# Proximity.net
KiCad netlist of a schematic drawn in Altium Designer
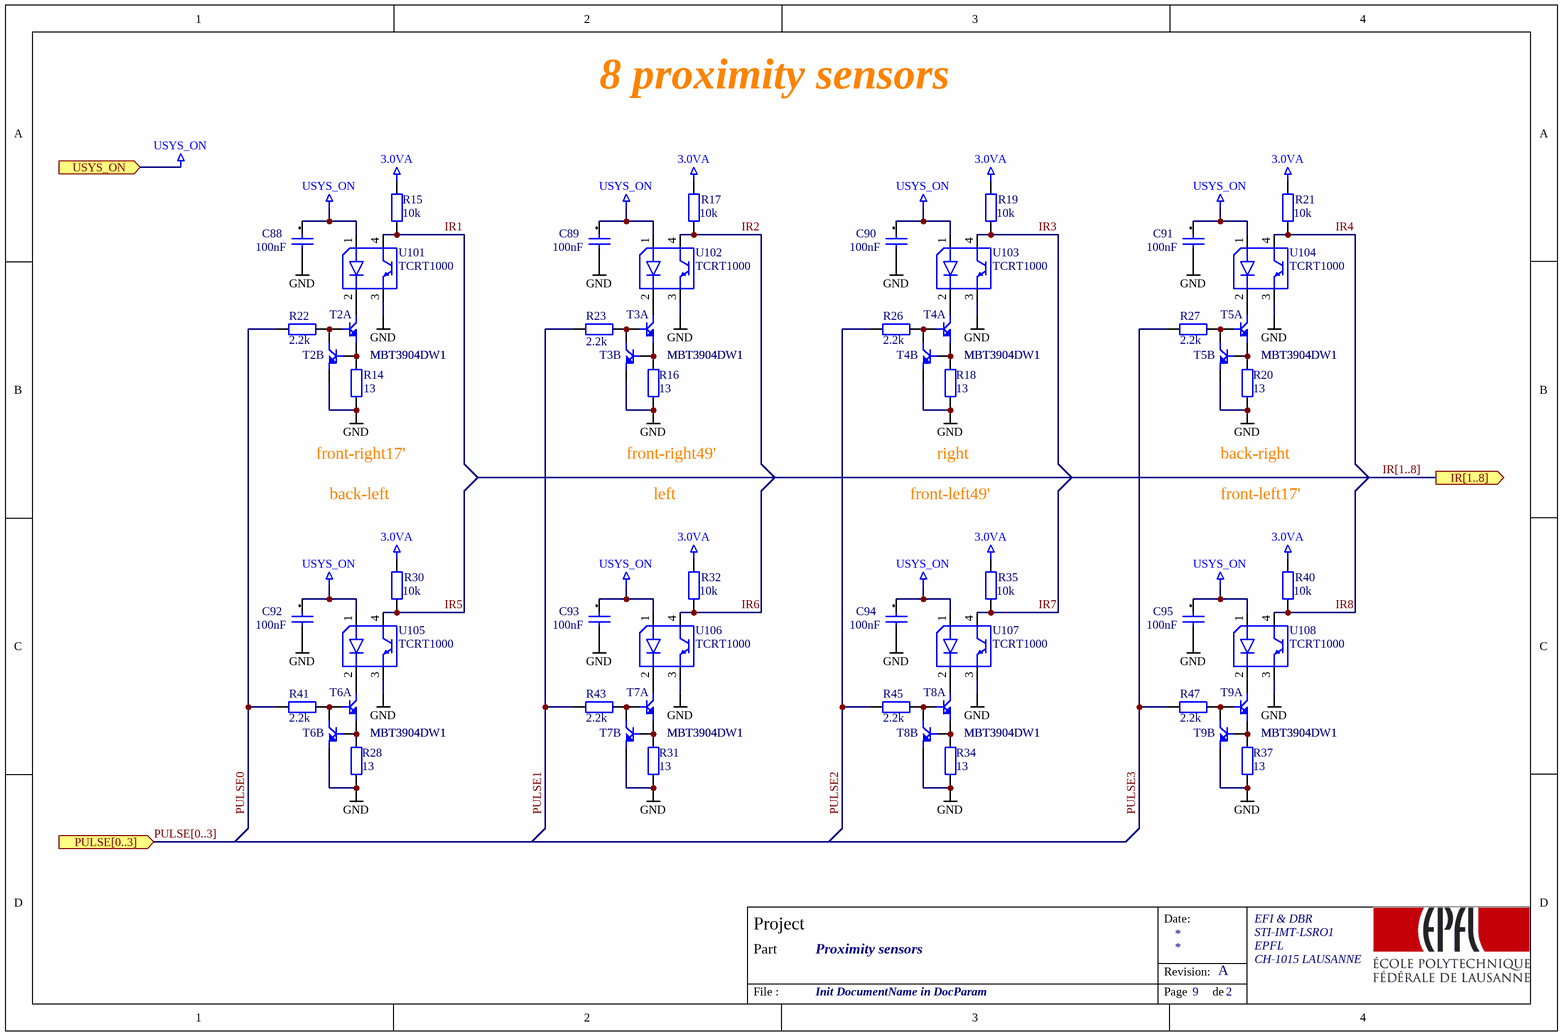
[diagram p0: Proximity.SchDoc]

(export (version "E")
  (design (tool "Eeschema 10.0.6"))
  (components
    (comp (ref "C88")
      (value "100nF")
      (footprint "ROB_0603")
      (description "Capacitor")
      (fields (field (name "MANUFACTURER") "Kemet") (field (name "VOLTAGE") "50"))
      (libsource (lib "LSRO1Altium") (part "CAP-NP"))
    )
    (comp (ref "C89")
      (value "100nF")
      (footprint "ROB_0603")
      (description "Capacitor")
      (fields (field (name "MANUFACTURER") "Kemet") (field (name "VOLTAGE") "50"))
      (libsource (lib "LSRO1Altium") (part "CAP-NP"))
    )
    (comp (ref "C90")
      (value "100nF")
      (footprint "ROB_0603")
      (description "Capacitor")
      (fields (field (name "MANUFACTURER") "Kemet") (field (name "VOLTAGE") "50"))
      (libsource (lib "LSRO1Altium") (part "CAP-NP"))
    )
    (comp (ref "C91")
      (value "100nF")
      (footprint "ROB_0603")
      (description "Capacitor")
      (fields (field (name "MANUFACTURER") "Kemet") (field (name "VOLTAGE") "50"))
      (libsource (lib "LSRO1Altium") (part "CAP-NP"))
    )
    (comp (ref "C92")
      (value "100nF")
      (footprint "ROB_0603")
      (description "Capacitor")
      (fields (field (name "MANUFACTURER") "Kemet") (field (name "VOLTAGE") "50"))
      (libsource (lib "LSRO1Altium") (part "CAP-NP"))
    )
    (comp (ref "C93")
      (value "100nF")
      (footprint "ROB_0603")
      (description "Capacitor")
      (fields (field (name "MANUFACTURER") "Kemet") (field (name "VOLTAGE") "50"))
      (libsource (lib "LSRO1Altium") (part "CAP-NP"))
    )
    (comp (ref "C94")
      (value "100nF")
      (footprint "ROB_0603")
      (description "Capacitor")
      (fields (field (name "MANUFACTURER") "Kemet") (field (name "VOLTAGE") "50"))
      (libsource (lib "LSRO1Altium") (part "CAP-NP"))
    )
    (comp (ref "C95")
      (value "100nF")
      (footprint "ROB_0603")
      (description "Capacitor")
      (fields (field (name "MANUFACTURER") "Kemet") (field (name "VOLTAGE") "50"))
      (libsource (lib "LSRO1Altium") (part "CAP-NP"))
    )
    (comp (ref "R14")
      (value "13")
      (footprint "ROB_0603")
      (description "Resistor")
      (fields (field (name "PUBLISHER") "Altium Limited"))
      (libsource (lib "") (part "Res2_2"))
    )
    (comp (ref "R15")
      (value "10k")
      (footprint "ROB_0603")
      (description "Resistor")
      (fields (field (name "PUBLISHER") "Altium Limited"))
      (libsource (lib "") (part "Res2_2"))
    )
    (comp (ref "R16")
      (value "13")
      (footprint "ROB_0603")
      (description "Resistor")
      (fields (field (name "PUBLISHER") "Altium Limited"))
      (libsource (lib "") (part "Res2_1"))
    )
    (comp (ref "R17")
      (value "10k")
      (footprint "ROB_0603")
      (description "Resistor")
      (fields (field (name "PUBLISHER") "Altium Limited"))
      (libsource (lib "") (part "Res2_2"))
    )
    (comp (ref "R18")
      (value "13")
      (footprint "ROB_0603")
      (description "Resistor")
      (fields (field (name "PUBLISHER") "Altium Limited"))
      (libsource (lib "") (part "Res2_1"))
    )
    (comp (ref "R19")
      (value "10k")
      (footprint "ROB_0603")
      (description "Resistor")
      (fields (field (name "PUBLISHER") "Altium Limited"))
      (libsource (lib "") (part "Res2_2"))
    )
    (comp (ref "R20")
      (value "13")
      (footprint "ROB_0603")
      (description "Resistor")
      (fields (field (name "PUBLISHER") "Altium Limited"))
      (libsource (lib "") (part "Res2_1"))
    )
    (comp (ref "R21")
      (value "10k")
      (footprint "ROB_0603")
      (description "Resistor")
      (fields (field (name "PUBLISHER") "Altium Limited"))
      (libsource (lib "") (part "Res2_2"))
    )
    (comp (ref "R22")
      (value "2.2k")
      (footprint "ROB_0603")
      (description "Resistor")
      (fields (field (name "PUBLISHER") "Altium Limited"))
      (libsource (lib "Miscellaneous Devices") (part "Res2"))
    )
    (comp (ref "R23")
      (value "2.2k")
      (footprint "ROB_0603")
      (description "Resistor")
      (fields (field (name "PUBLISHER") "Altium Limited"))
      (libsource (lib "Miscellaneous Devices") (part "Res2"))
    )
    (comp (ref "R26")
      (value "2.2k")
      (footprint "ROB_0603")
      (description "Resistor")
      (fields (field (name "PUBLISHER") "Altium Limited"))
      (libsource (lib "Miscellaneous Devices") (part "Res2"))
    )
    (comp (ref "R27")
      (value "2.2k")
      (footprint "ROB_0603")
      (description "Resistor")
      (fields (field (name "PUBLISHER") "Altium Limited"))
      (libsource (lib "Miscellaneous Devices") (part "Res2"))
    )
    (comp (ref "R28")
      (value "13")
      (footprint "ROB_0603")
      (description "Resistor")
      (fields (field (name "PUBLISHER") "Altium Limited"))
      (libsource (lib "") (part "Res2_1"))
    )
    (comp (ref "R30")
      (value "10k")
      (footprint "ROB_0603")
      (description "Resistor")
      (fields (field (name "PUBLISHER") "Altium Limited"))
      (libsource (lib "") (part "Res2_2"))
    )
    (comp (ref "R31")
      (value "13")
      (footprint "ROB_0603")
      (description "Resistor")
      (fields (field (name "PUBLISHER") "Altium Limited"))
      (libsource (lib "") (part "Res2_1"))
    )
    (comp (ref "R32")
      (value "10k")
      (footprint "ROB_0603")
      (description "Resistor")
      (fields (field (name "PUBLISHER") "Altium Limited"))
      (libsource (lib "") (part "Res2_2"))
    )
    (comp (ref "R34")
      (value "13")
      (footprint "ROB_0603")
      (description "Resistor")
      (fields (field (name "PUBLISHER") "Altium Limited"))
      (libsource (lib "") (part "Res2_1"))
    )
    (comp (ref "R35")
      (value "10k")
      (footprint "ROB_0603")
      (description "Resistor")
      (fields (field (name "PUBLISHER") "Altium Limited"))
      (libsource (lib "") (part "Res2_2"))
    )
    (comp (ref "R37")
      (value "13")
      (footprint "ROB_0603")
      (description "Resistor")
      (fields (field (name "PUBLISHER") "Altium Limited"))
      (libsource (lib "") (part "Res2_1"))
    )
    (comp (ref "R40")
      (value "10k")
      (footprint "ROB_0603")
      (description "Resistor")
      (fields (field (name "PUBLISHER") "Altium Limited"))
      (libsource (lib "") (part "Res2_2"))
    )
    (comp (ref "R41")
      (value "2.2k")
      (footprint "ROB_0603")
      (description "Resistor")
      (fields (field (name "PUBLISHER") "Altium Limited"))
      (libsource (lib "Miscellaneous Devices") (part "Res2"))
    )
    (comp (ref "R43")
      (value "2.2k")
      (footprint "ROB_0603")
      (description "Resistor")
      (fields (field (name "PUBLISHER") "Altium Limited"))
      (libsource (lib "Miscellaneous Devices") (part "Res2"))
    )
    (comp (ref "R45")
      (value "2.2k")
      (footprint "ROB_0603")
      (description "Resistor")
      (fields (field (name "PUBLISHER") "Altium Limited"))
      (libsource (lib "Miscellaneous Devices") (part "Res2"))
    )
    (comp (ref "R47")
      (value "2.2k")
      (footprint "ROB_0603")
      (description "Resistor")
      (fields (field (name "PUBLISHER") "Altium Limited"))
      (libsource (lib "Miscellaneous Devices") (part "Res2"))
    )
    (comp (ref "T2")
      (value "MBT3904DW1")
      (footprint "SC70-6")
      (description "Dual NPN 0.2A")
      (fields (field (name "PUBLISHER") "Altium Limited"))
      (libsource (lib "Rob_sch") (part "MBT3904DW1"))
    )
    (comp (ref "T3")
      (value "MBT3904DW1")
      (footprint "SC70-6")
      (description "Dual NPN 0.2A")
      (fields (field (name "PUBLISHER") "Altium Limited"))
      (libsource (lib "Rob_sch") (part "MBT3904DW1"))
    )
    (comp (ref "T4")
      (value "MBT3904DW1")
      (footprint "SC70-6")
      (description "Dual NPN 0.2A")
      (fields (field (name "PUBLISHER") "Altium Limited"))
      (libsource (lib "Rob_sch") (part "MBT3904DW1"))
    )
    (comp (ref "T5")
      (value "MBT3904DW1")
      (footprint "SC70-6")
      (description "Dual NPN 0.2A")
      (fields (field (name "PUBLISHER") "Altium Limited"))
      (libsource (lib "Rob_sch") (part "MBT3904DW1"))
    )
    (comp (ref "T6")
      (value "MBT3904DW1")
      (footprint "SC70-6")
      (description "Dual NPN 0.2A")
      (fields (field (name "PUBLISHER") "Altium Limited"))
      (libsource (lib "Rob_sch") (part "MBT3904DW1"))
    )
    (comp (ref "T7")
      (value "MBT3904DW1")
      (footprint "SC70-6")
      (description "Dual NPN 0.2A")
      (fields (field (name "PUBLISHER") "Altium Limited"))
      (libsource (lib "Rob_sch") (part "MBT3904DW1"))
    )
    (comp (ref "T8")
      (value "MBT3904DW1")
      (footprint "SC70-6")
      (description "Dual NPN 0.2A")
      (fields (field (name "PUBLISHER") "Altium Limited"))
      (libsource (lib "Rob_sch") (part "MBT3904DW1"))
    )
    (comp (ref "T9")
      (value "MBT3904DW1")
      (footprint "SC70-6")
      (description "Dual NPN 0.2A")
      (fields (field (name "PUBLISHER") "Altium Limited"))
      (libsource (lib "Rob_sch") (part "MBT3904DW1"))
    )
    (comp (ref "U101")
      (value "TCRT1000")
      (footprint "TCRT1000")
      (description "Reflective Optical Sensor. bottom but top pins must remain 1.4 mm")
      (libsource (lib "Rob_sch") (part "TCRT1000"))
    )
    (comp (ref "U102")
      (value "TCRT1000")
      (footprint "TCRT1000")
      (description "Reflective Optical Sensor with Transistor Output")
      (libsource (lib "Rob_sch") (part "TCRT1000"))
    )
    (comp (ref "U103")
      (value "TCRT1000")
      (footprint "TCRT1000")
      (description "Reflective Optical Sensor with Transistor Output")
      (libsource (lib "Rob_sch") (part "TCRT1000"))
    )
    (comp (ref "U104")
      (value "TCRT1000")
      (footprint "TCRT1000")
      (description "Reflective Optical Sensor with Transistor Output")
      (libsource (lib "Rob_sch") (part "TCRT1000"))
    )
    (comp (ref "U105")
      (value "TCRT1000")
      (footprint "TCRT1000")
      (description "Reflective Optical Sensor with Transistor Output")
      (libsource (lib "Rob_sch") (part "TCRT1000"))
    )
    (comp (ref "U106")
      (value "TCRT1000")
      (footprint "TCRT1000")
      (description "Reflective Optical Sensor with Transistor Output")
      (libsource (lib "Rob_sch") (part "TCRT1000"))
    )
    (comp (ref "U107")
      (value "TCRT1000")
      (footprint "TCRT1000")
      (description "Reflective Optical Sensor with Transistor Output")
      (libsource (lib "Rob_sch") (part "TCRT1000"))
    )
    (comp (ref "U108")
      (value "TCRT1000")
      (footprint "TCRT1000")
      (description "Reflective Optical Sensor with Transistor Output")
      (libsource (lib "Rob_sch") (part "TCRT1000"))
    )
  )
  (nets
    (net (code "1") (name "/IR1") (class "Default")
      (node (ref "R15") (pin "2") (pinfunction "2_2") (pintype "passive"))
      (node (ref "U101") (pin "4") (pinfunction "C_4") (pintype "passive"))
    )
    (net (code "2") (name "/IR2") (class "Default")
      (node (ref "R17") (pin "2") (pinfunction "2_2") (pintype "passive"))
      (node (ref "U102") (pin "4") (pinfunction "C_4") (pintype "passive"))
    )
    (net (code "3") (name "/IR3") (class "Default")
      (node (ref "R19") (pin "2") (pinfunction "2_2") (pintype "passive"))
      (node (ref "U103") (pin "4") (pinfunction "C_4") (pintype "passive"))
    )
    (net (code "4") (name "/IR4") (class "Default")
      (node (ref "R21") (pin "2") (pinfunction "2_2") (pintype "passive"))
      (node (ref "U104") (pin "4") (pinfunction "C_4") (pintype "passive"))
    )
    (net (code "5") (name "/IR5") (class "Default")
      (node (ref "R30") (pin "2") (pinfunction "2_2") (pintype "passive"))
      (node (ref "U105") (pin "4") (pinfunction "C_4") (pintype "passive"))
    )
    (net (code "6") (name "/IR6") (class "Default")
      (node (ref "R32") (pin "2") (pinfunction "2_2") (pintype "passive"))
      (node (ref "U106") (pin "4") (pinfunction "C_4") (pintype "passive"))
    )
    (net (code "7") (name "/IR7") (class "Default")
      (node (ref "R35") (pin "2") (pinfunction "2_2") (pintype "passive"))
      (node (ref "U107") (pin "4") (pinfunction "C_4") (pintype "passive"))
    )
    (net (code "8") (name "/IR8") (class "Default")
      (node (ref "R40") (pin "2") (pinfunction "2_2") (pintype "passive"))
      (node (ref "U108") (pin "4") (pinfunction "C_4") (pintype "passive"))
    )
    (net (code "10") (name "/PULSE0") (class "Default")
      (node (ref "R22") (pin "1") (pinfunction "1_1") (pintype "passive"))
      (node (ref "R41") (pin "1") (pinfunction "1_1") (pintype "passive"))
    )
    (net (code "11") (name "/PULSE1") (class "Default")
      (node (ref "R23") (pin "1") (pinfunction "1_1") (pintype "passive"))
      (node (ref "R43") (pin "1") (pinfunction "1_1") (pintype "passive"))
    )
    (net (code "12") (name "/PULSE2") (class "Default")
      (node (ref "R26") (pin "1") (pinfunction "1_1") (pintype "passive"))
      (node (ref "R45") (pin "1") (pinfunction "1_1") (pintype "passive"))
    )
    (net (code "13") (name "/PULSE3") (class "Default")
      (node (ref "R27") (pin "1") (pinfunction "1_1") (pintype "passive"))
      (node (ref "R47") (pin "1") (pinfunction "1_1") (pintype "passive"))
    )
    (net (code "15") (name "3.0VA") (class "Default")
      (node (ref "R15") (pin "1") (pinfunction "1_1") (pintype "passive"))
      (node (ref "R17") (pin "1") (pinfunction "1_1") (pintype "passive"))
      (node (ref "R19") (pin "1") (pinfunction "1_1") (pintype "passive"))
      (node (ref "R21") (pin "1") (pinfunction "1_1") (pintype "passive"))
      (node (ref "R30") (pin "1") (pinfunction "1_1") (pintype "passive"))
      (node (ref "R32") (pin "1") (pinfunction "1_1") (pintype "passive"))
      (node (ref "R35") (pin "1") (pinfunction "1_1") (pintype "passive"))
      (node (ref "R40") (pin "1") (pinfunction "1_1") (pintype "passive"))
    )
    (net (code "16") (name "GND") (class "Default")
      (node (ref "C88") (pin "2") (pinfunction "2_2") (pintype "passive"))
      (node (ref "C89") (pin "2") (pinfunction "2_2") (pintype "passive"))
      (node (ref "C90") (pin "2") (pinfunction "2_2") (pintype "passive"))
      (node (ref "C91") (pin "2") (pinfunction "2_2") (pintype "passive"))
      (node (ref "C92") (pin "2") (pinfunction "2_2") (pintype "passive"))
      (node (ref "C93") (pin "2") (pinfunction "2_2") (pintype "passive"))
      (node (ref "C94") (pin "2") (pinfunction "2_2") (pintype "passive"))
      (node (ref "C95") (pin "2") (pinfunction "2_2") (pintype "passive"))
      (node (ref "R14") (pin "2") (pinfunction "2_2") (pintype "passive"))
      (node (ref "R16") (pin "1") (pinfunction "1_1") (pintype "passive"))
      (node (ref "R18") (pin "1") (pinfunction "1_1") (pintype "passive"))
      (node (ref "R20") (pin "1") (pinfunction "1_1") (pintype "passive"))
      (node (ref "R28") (pin "1") (pinfunction "1_1") (pintype "passive"))
      (node (ref "R31") (pin "1") (pinfunction "1_1") (pintype "passive"))
      (node (ref "R34") (pin "1") (pinfunction "1_1") (pintype "passive"))
      (node (ref "R37") (pin "1") (pinfunction "1_1") (pintype "passive"))
      (node (ref "T2") (pin "4") (pinfunction "E2_4") (pintype "passive"))
      (node (ref "T3") (pin "4") (pinfunction "E2_4") (pintype "passive"))
      (node (ref "T4") (pin "4") (pinfunction "E2_4") (pintype "passive"))
      (node (ref "T5") (pin "4") (pinfunction "E2_4") (pintype "passive"))
      (node (ref "T6") (pin "4") (pinfunction "E2_4") (pintype "passive"))
      (node (ref "T7") (pin "4") (pinfunction "E2_4") (pintype "passive"))
      (node (ref "T8") (pin "4") (pinfunction "E2_4") (pintype "passive"))
      (node (ref "T9") (pin "4") (pinfunction "E2_4") (pintype "passive"))
      (node (ref "U101") (pin "3") (pinfunction "E_3") (pintype "passive"))
      (node (ref "U102") (pin "3") (pinfunction "E_3") (pintype "passive"))
      (node (ref "U103") (pin "3") (pinfunction "E_3") (pintype "passive"))
      (node (ref "U104") (pin "3") (pinfunction "E_3") (pintype "passive"))
      (node (ref "U105") (pin "3") (pinfunction "E_3") (pintype "passive"))
      (node (ref "U106") (pin "3") (pinfunction "E_3") (pintype "passive"))
      (node (ref "U107") (pin "3") (pinfunction "E_3") (pintype "passive"))
      (node (ref "U108") (pin "3") (pinfunction "E_3") (pintype "passive"))
    )
    (net (code "17") (name "Net-(T2A-B1)") (class "Default")
      (node (ref "R22") (pin "2") (pinfunction "2_2") (pintype "passive"))
      (node (ref "T2") (pin "2") (pinfunction "B1_2") (pintype "passive"))
      (node (ref "T2") (pin "3") (pinfunction "C2_3") (pintype "passive"))
    )
    (net (code "18") (name "Net-(T2A-C1)") (class "Default")
      (node (ref "T2") (pin "6") (pinfunction "C1_6") (pintype "passive"))
      (node (ref "U101") (pin "2") (pinfunction "K_2") (pintype "passive"))
    )
    (net (code "19") (name "Net-(T2A-E1)") (class "Default")
      (node (ref "R14") (pin "1") (pinfunction "1_1") (pintype "passive"))
      (node (ref "T2") (pin "1") (pinfunction "E1_1") (pintype "passive"))
      (node (ref "T2") (pin "5") (pinfunction "B2_5") (pintype "passive"))
    )
    (net (code "20") (name "Net-(T3A-B1)") (class "Default")
      (node (ref "R23") (pin "2") (pinfunction "2_2") (pintype "passive"))
      (node (ref "T3") (pin "2") (pinfunction "B1_2") (pintype "passive"))
      (node (ref "T3") (pin "3") (pinfunction "C2_3") (pintype "passive"))
    )
    (net (code "21") (name "Net-(T3A-C1)") (class "Default")
      (node (ref "T3") (pin "6") (pinfunction "C1_6") (pintype "passive"))
      (node (ref "U102") (pin "2") (pinfunction "K_2") (pintype "passive"))
    )
    (net (code "22") (name "Net-(T3A-E1)") (class "Default")
      (node (ref "R16") (pin "2") (pinfunction "2_2") (pintype "passive"))
      (node (ref "T3") (pin "1") (pinfunction "E1_1") (pintype "passive"))
      (node (ref "T3") (pin "5") (pinfunction "B2_5") (pintype "passive"))
    )
    (net (code "23") (name "Net-(T4A-B1)") (class "Default")
      (node (ref "R26") (pin "2") (pinfunction "2_2") (pintype "passive"))
      (node (ref "T4") (pin "2") (pinfunction "B1_2") (pintype "passive"))
      (node (ref "T4") (pin "3") (pinfunction "C2_3") (pintype "passive"))
    )
    (net (code "24") (name "Net-(T4A-C1)") (class "Default")
      (node (ref "T4") (pin "6") (pinfunction "C1_6") (pintype "passive"))
      (node (ref "U103") (pin "2") (pinfunction "K_2") (pintype "passive"))
    )
    (net (code "25") (name "Net-(T4A-E1)") (class "Default")
      (node (ref "R18") (pin "2") (pinfunction "2_2") (pintype "passive"))
      (node (ref "T4") (pin "1") (pinfunction "E1_1") (pintype "passive"))
      (node (ref "T4") (pin "5") (pinfunction "B2_5") (pintype "passive"))
    )
    (net (code "26") (name "Net-(T5A-B1)") (class "Default")
      (node (ref "R27") (pin "2") (pinfunction "2_2") (pintype "passive"))
      (node (ref "T5") (pin "2") (pinfunction "B1_2") (pintype "passive"))
      (node (ref "T5") (pin "3") (pinfunction "C2_3") (pintype "passive"))
    )
    (net (code "27") (name "Net-(T5A-C1)") (class "Default")
      (node (ref "T5") (pin "6") (pinfunction "C1_6") (pintype "passive"))
      (node (ref "U104") (pin "2") (pinfunction "K_2") (pintype "passive"))
    )
    (net (code "28") (name "Net-(T5A-E1)") (class "Default")
      (node (ref "R20") (pin "2") (pinfunction "2_2") (pintype "passive"))
      (node (ref "T5") (pin "1") (pinfunction "E1_1") (pintype "passive"))
      (node (ref "T5") (pin "5") (pinfunction "B2_5") (pintype "passive"))
    )
    (net (code "29") (name "Net-(T6A-B1)") (class "Default")
      (node (ref "R41") (pin "2") (pinfunction "2_2") (pintype "passive"))
      (node (ref "T6") (pin "2") (pinfunction "B1_2") (pintype "passive"))
      (node (ref "T6") (pin "3") (pinfunction "C2_3") (pintype "passive"))
    )
    (net (code "30") (name "Net-(T6A-C1)") (class "Default")
      (node (ref "T6") (pin "6") (pinfunction "C1_6") (pintype "passive"))
      (node (ref "U105") (pin "2") (pinfunction "K_2") (pintype "passive"))
    )
    (net (code "31") (name "Net-(T6A-E1)") (class "Default")
      (node (ref "R28") (pin "2") (pinfunction "2_2") (pintype "passive"))
      (node (ref "T6") (pin "1") (pinfunction "E1_1") (pintype "passive"))
      (node (ref "T6") (pin "5") (pinfunction "B2_5") (pintype "passive"))
    )
    (net (code "32") (name "Net-(T7A-B1)") (class "Default")
      (node (ref "R43") (pin "2") (pinfunction "2_2") (pintype "passive"))
      (node (ref "T7") (pin "2") (pinfunction "B1_2") (pintype "passive"))
      (node (ref "T7") (pin "3") (pinfunction "C2_3") (pintype "passive"))
    )
    (net (code "33") (name "Net-(T7A-C1)") (class "Default")
      (node (ref "T7") (pin "6") (pinfunction "C1_6") (pintype "passive"))
      (node (ref "U106") (pin "2") (pinfunction "K_2") (pintype "passive"))
    )
    (net (code "34") (name "Net-(T7A-E1)") (class "Default")
      (node (ref "R31") (pin "2") (pinfunction "2_2") (pintype "passive"))
      (node (ref "T7") (pin "1") (pinfunction "E1_1") (pintype "passive"))
      (node (ref "T7") (pin "5") (pinfunction "B2_5") (pintype "passive"))
    )
    (net (code "35") (name "Net-(T8A-B1)") (class "Default")
      (node (ref "R45") (pin "2") (pinfunction "2_2") (pintype "passive"))
      (node (ref "T8") (pin "2") (pinfunction "B1_2") (pintype "passive"))
      (node (ref "T8") (pin "3") (pinfunction "C2_3") (pintype "passive"))
    )
    (net (code "36") (name "Net-(T8A-C1)") (class "Default")
      (node (ref "T8") (pin "6") (pinfunction "C1_6") (pintype "passive"))
      (node (ref "U107") (pin "2") (pinfunction "K_2") (pintype "passive"))
    )
    (net (code "37") (name "Net-(T8A-E1)") (class "Default")
      (node (ref "R34") (pin "2") (pinfunction "2_2") (pintype "passive"))
      (node (ref "T8") (pin "1") (pinfunction "E1_1") (pintype "passive"))
      (node (ref "T8") (pin "5") (pinfunction "B2_5") (pintype "passive"))
    )
    (net (code "38") (name "Net-(T9A-B1)") (class "Default")
      (node (ref "R47") (pin "2") (pinfunction "2_2") (pintype "passive"))
      (node (ref "T9") (pin "2") (pinfunction "B1_2") (pintype "passive"))
      (node (ref "T9") (pin "3") (pinfunction "C2_3") (pintype "passive"))
    )
    (net (code "39") (name "Net-(T9A-C1)") (class "Default")
      (node (ref "T9") (pin "6") (pinfunction "C1_6") (pintype "passive"))
      (node (ref "U108") (pin "2") (pinfunction "K_2") (pintype "passive"))
    )
    (net (code "40") (name "Net-(T9A-E1)") (class "Default")
      (node (ref "R37") (pin "2") (pinfunction "2_2") (pintype "passive"))
      (node (ref "T9") (pin "1") (pinfunction "E1_1") (pintype "passive"))
      (node (ref "T9") (pin "5") (pinfunction "B2_5") (pintype "passive"))
    )
    (net (code "41") (name "USYS_ON") (class "Default")
      (node (ref "C88") (pin "1") (pinfunction "1_1") (pintype "passive"))
      (node (ref "C89") (pin "1") (pinfunction "1_1") (pintype "passive"))
      (node (ref "C90") (pin "1") (pinfunction "1_1") (pintype "passive"))
      (node (ref "C91") (pin "1") (pinfunction "1_1") (pintype "passive"))
      (node (ref "C92") (pin "1") (pinfunction "1_1") (pintype "passive"))
      (node (ref "C93") (pin "1") (pinfunction "1_1") (pintype "passive"))
      (node (ref "C94") (pin "1") (pinfunction "1_1") (pintype "passive"))
      (node (ref "C95") (pin "1") (pinfunction "1_1") (pintype "passive"))
      (node (ref "U101") (pin "1") (pinfunction "A_1") (pintype "passive"))
      (node (ref "U102") (pin "1") (pinfunction "A_1") (pintype "passive"))
      (node (ref "U103") (pin "1") (pinfunction "A_1") (pintype "passive"))
      (node (ref "U104") (pin "1") (pinfunction "A_1") (pintype "passive"))
      (node (ref "U105") (pin "1") (pinfunction "A_1") (pintype "passive"))
      (node (ref "U106") (pin "1") (pinfunction "A_1") (pintype "passive"))
      (node (ref "U107") (pin "1") (pinfunction "A_1") (pintype "passive"))
      (node (ref "U108") (pin "1") (pinfunction "A_1") (pintype "passive"))
    )
  )
)
